# 2_MUX.net
KiCad netlist of a schematic drawn in Altium Designer
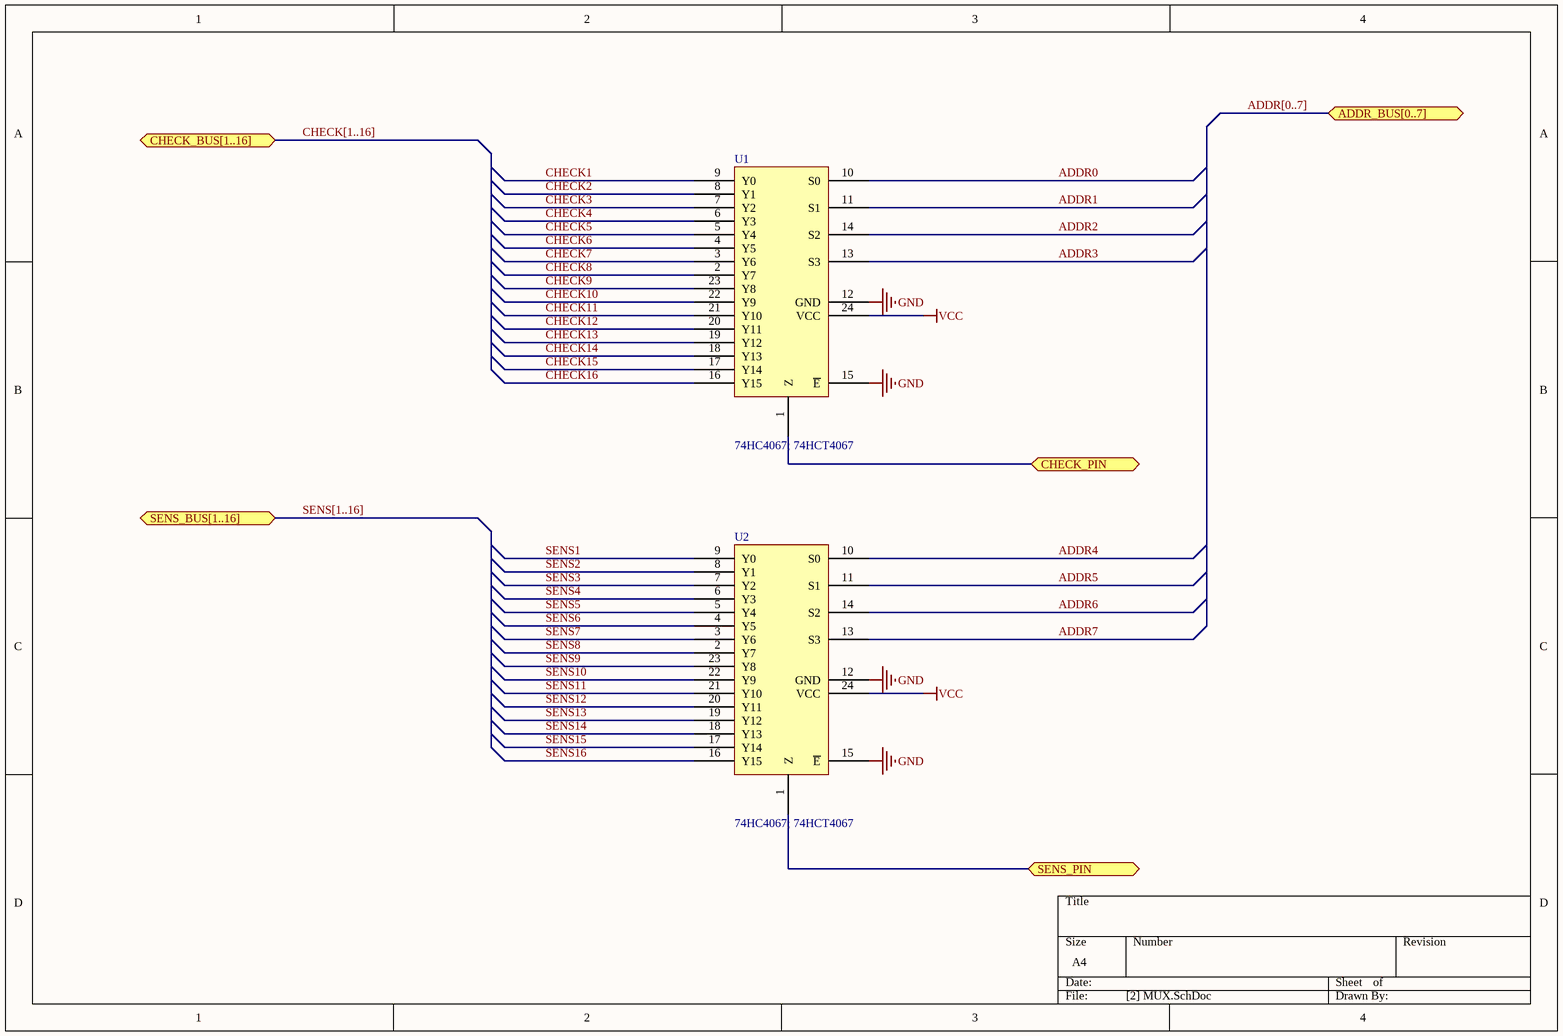
[diagram p0: [2] MUX.SchDoc]

(export (version "E")
  (design (tool "Eeschema 10.0.6"))
  (components
    (comp (ref "U1")
      (value "74HC4067; 74HCT4067")
      (footprint "SO24")
      (description "16-channel analog multiplexer/demultiplexer")
      (libsource (lib "PCB_Project") (part "74HC4067; 74HCT4067"))
    )
    (comp (ref "U2")
      (value "74HC4067; 74HCT4067")
      (footprint "SO24")
      (description "16-channel analog multiplexer/demultiplexer")
      (libsource (lib "PCB_Project") (part "74HC4067; 74HCT4067"))
    )
  )
  (nets
    (net (code "1") (name "/ADDR0") (class "Default")
      (node (ref "U1") (pin "10") (pinfunction "S0_10") (pintype "passive"))
    )
    (net (code "2") (name "/ADDR1") (class "Default")
      (node (ref "U1") (pin "11") (pinfunction "S1_11") (pintype "passive"))
    )
    (net (code "3") (name "/ADDR2") (class "Default")
      (node (ref "U1") (pin "14") (pinfunction "S2_14") (pintype "passive"))
    )
    (net (code "4") (name "/ADDR3") (class "Default")
      (node (ref "U1") (pin "13") (pinfunction "S3_13") (pintype "passive"))
    )
    (net (code "5") (name "/ADDR4") (class "Default")
      (node (ref "U2") (pin "10") (pinfunction "S0_10") (pintype "passive"))
    )
    (net (code "6") (name "/ADDR5") (class "Default")
      (node (ref "U2") (pin "11") (pinfunction "S1_11") (pintype "passive"))
    )
    (net (code "7") (name "/ADDR6") (class "Default")
      (node (ref "U2") (pin "14") (pinfunction "S2_14") (pintype "passive"))
    )
    (net (code "8") (name "/ADDR7") (class "Default")
      (node (ref "U2") (pin "13") (pinfunction "S3_13") (pintype "passive"))
    )
    (net (code "10") (name "/CHECK1") (class "Default")
      (node (ref "U1") (pin "9") (pinfunction "Y0_9") (pintype "passive"))
    )
    (net (code "11") (name "/CHECK2") (class "Default")
      (node (ref "U1") (pin "8") (pinfunction "Y1_8") (pintype "passive"))
    )
    (net (code "12") (name "/CHECK3") (class "Default")
      (node (ref "U1") (pin "7") (pinfunction "Y2_7") (pintype "passive"))
    )
    (net (code "13") (name "/CHECK4") (class "Default")
      (node (ref "U1") (pin "6") (pinfunction "Y3_6") (pintype "passive"))
    )
    (net (code "14") (name "/CHECK5") (class "Default")
      (node (ref "U1") (pin "5") (pinfunction "Y4_5") (pintype "passive"))
    )
    (net (code "15") (name "/CHECK6") (class "Default")
      (node (ref "U1") (pin "4") (pinfunction "Y5_4") (pintype "passive"))
    )
    (net (code "16") (name "/CHECK7") (class "Default")
      (node (ref "U1") (pin "3") (pinfunction "Y6_3") (pintype "passive"))
    )
    (net (code "17") (name "/CHECK8") (class "Default")
      (node (ref "U1") (pin "2") (pinfunction "Y7_2") (pintype "passive"))
    )
    (net (code "18") (name "/CHECK9") (class "Default")
      (node (ref "U1") (pin "23") (pinfunction "Y8_23") (pintype "passive"))
    )
    (net (code "19") (name "/CHECK10") (class "Default")
      (node (ref "U1") (pin "22") (pinfunction "Y9_22") (pintype "passive"))
    )
    (net (code "20") (name "/CHECK11") (class "Default")
      (node (ref "U1") (pin "21") (pinfunction "Y10_21") (pintype "passive"))
    )
    (net (code "21") (name "/CHECK12") (class "Default")
      (node (ref "U1") (pin "20") (pinfunction "Y11_20") (pintype "passive"))
    )
    (net (code "22") (name "/CHECK13") (class "Default")
      (node (ref "U1") (pin "19") (pinfunction "Y12_19") (pintype "passive"))
    )
    (net (code "23") (name "/CHECK14") (class "Default")
      (node (ref "U1") (pin "18") (pinfunction "Y13_18") (pintype "passive"))
    )
    (net (code "24") (name "/CHECK15") (class "Default")
      (node (ref "U1") (pin "17") (pinfunction "Y14_17") (pintype "passive"))
    )
    (net (code "25") (name "/CHECK16") (class "Default")
      (node (ref "U1") (pin "16") (pinfunction "Y15_16") (pintype "passive"))
    )
    (net (code "27") (name "/CHECK_PIN") (class "Default")
      (node (ref "U1") (pin "1") (pinfunction "Z_1") (pintype "passive"))
    )
    (net (code "28") (name "/SENS1") (class "Default")
      (node (ref "U2") (pin "9") (pinfunction "Y0_9") (pintype "passive"))
    )
    (net (code "29") (name "/SENS2") (class "Default")
      (node (ref "U2") (pin "8") (pinfunction "Y1_8") (pintype "passive"))
    )
    (net (code "30") (name "/SENS3") (class "Default")
      (node (ref "U2") (pin "7") (pinfunction "Y2_7") (pintype "passive"))
    )
    (net (code "31") (name "/SENS4") (class "Default")
      (node (ref "U2") (pin "6") (pinfunction "Y3_6") (pintype "passive"))
    )
    (net (code "32") (name "/SENS5") (class "Default")
      (node (ref "U2") (pin "5") (pinfunction "Y4_5") (pintype "passive"))
    )
    (net (code "33") (name "/SENS6") (class "Default")
      (node (ref "U2") (pin "4") (pinfunction "Y5_4") (pintype "passive"))
    )
    (net (code "34") (name "/SENS7") (class "Default")
      (node (ref "U2") (pin "3") (pinfunction "Y6_3") (pintype "passive"))
    )
    (net (code "35") (name "/SENS8") (class "Default")
      (node (ref "U2") (pin "2") (pinfunction "Y7_2") (pintype "passive"))
    )
    (net (code "36") (name "/SENS9") (class "Default")
      (node (ref "U2") (pin "23") (pinfunction "Y8_23") (pintype "passive"))
    )
    (net (code "37") (name "/SENS10") (class "Default")
      (node (ref "U2") (pin "22") (pinfunction "Y9_22") (pintype "passive"))
    )
    (net (code "38") (name "/SENS11") (class "Default")
      (node (ref "U2") (pin "21") (pinfunction "Y10_21") (pintype "passive"))
    )
    (net (code "39") (name "/SENS12") (class "Default")
      (node (ref "U2") (pin "20") (pinfunction "Y11_20") (pintype "passive"))
    )
    (net (code "40") (name "/SENS13") (class "Default")
      (node (ref "U2") (pin "19") (pinfunction "Y12_19") (pintype "passive"))
    )
    (net (code "41") (name "/SENS14") (class "Default")
      (node (ref "U2") (pin "18") (pinfunction "Y13_18") (pintype "passive"))
    )
    (net (code "42") (name "/SENS15") (class "Default")
      (node (ref "U2") (pin "17") (pinfunction "Y14_17") (pintype "passive"))
    )
    (net (code "43") (name "/SENS16") (class "Default")
      (node (ref "U2") (pin "16") (pinfunction "Y15_16") (pintype "passive"))
    )
    (net (code "45") (name "/SENS_PIN") (class "Default")
      (node (ref "U2") (pin "1") (pinfunction "Z_1") (pintype "passive"))
    )
    (net (code "46") (name "GND") (class "Default")
      (node (ref "U1") (pin "12") (pinfunction "GND_12") (pintype "passive"))
      (node (ref "U1") (pin "15") (pinfunction "~{E}_15") (pintype "passive"))
      (node (ref "U2") (pin "12") (pinfunction "GND_12") (pintype "passive"))
      (node (ref "U2") (pin "15") (pinfunction "~{E}_15") (pintype "passive"))
    )
    (net (code "47") (name "VCC") (class "Default")
      (node (ref "U1") (pin "24") (pinfunction "VCC_24") (pintype "passive"))
      (node (ref "U2") (pin "24") (pinfunction "VCC_24") (pintype "passive"))
    )
  )
)
